# 9xVoice_MikeB_SMD_v1_0b.net
KiCad netlist of a schematic drawn in EAGLE
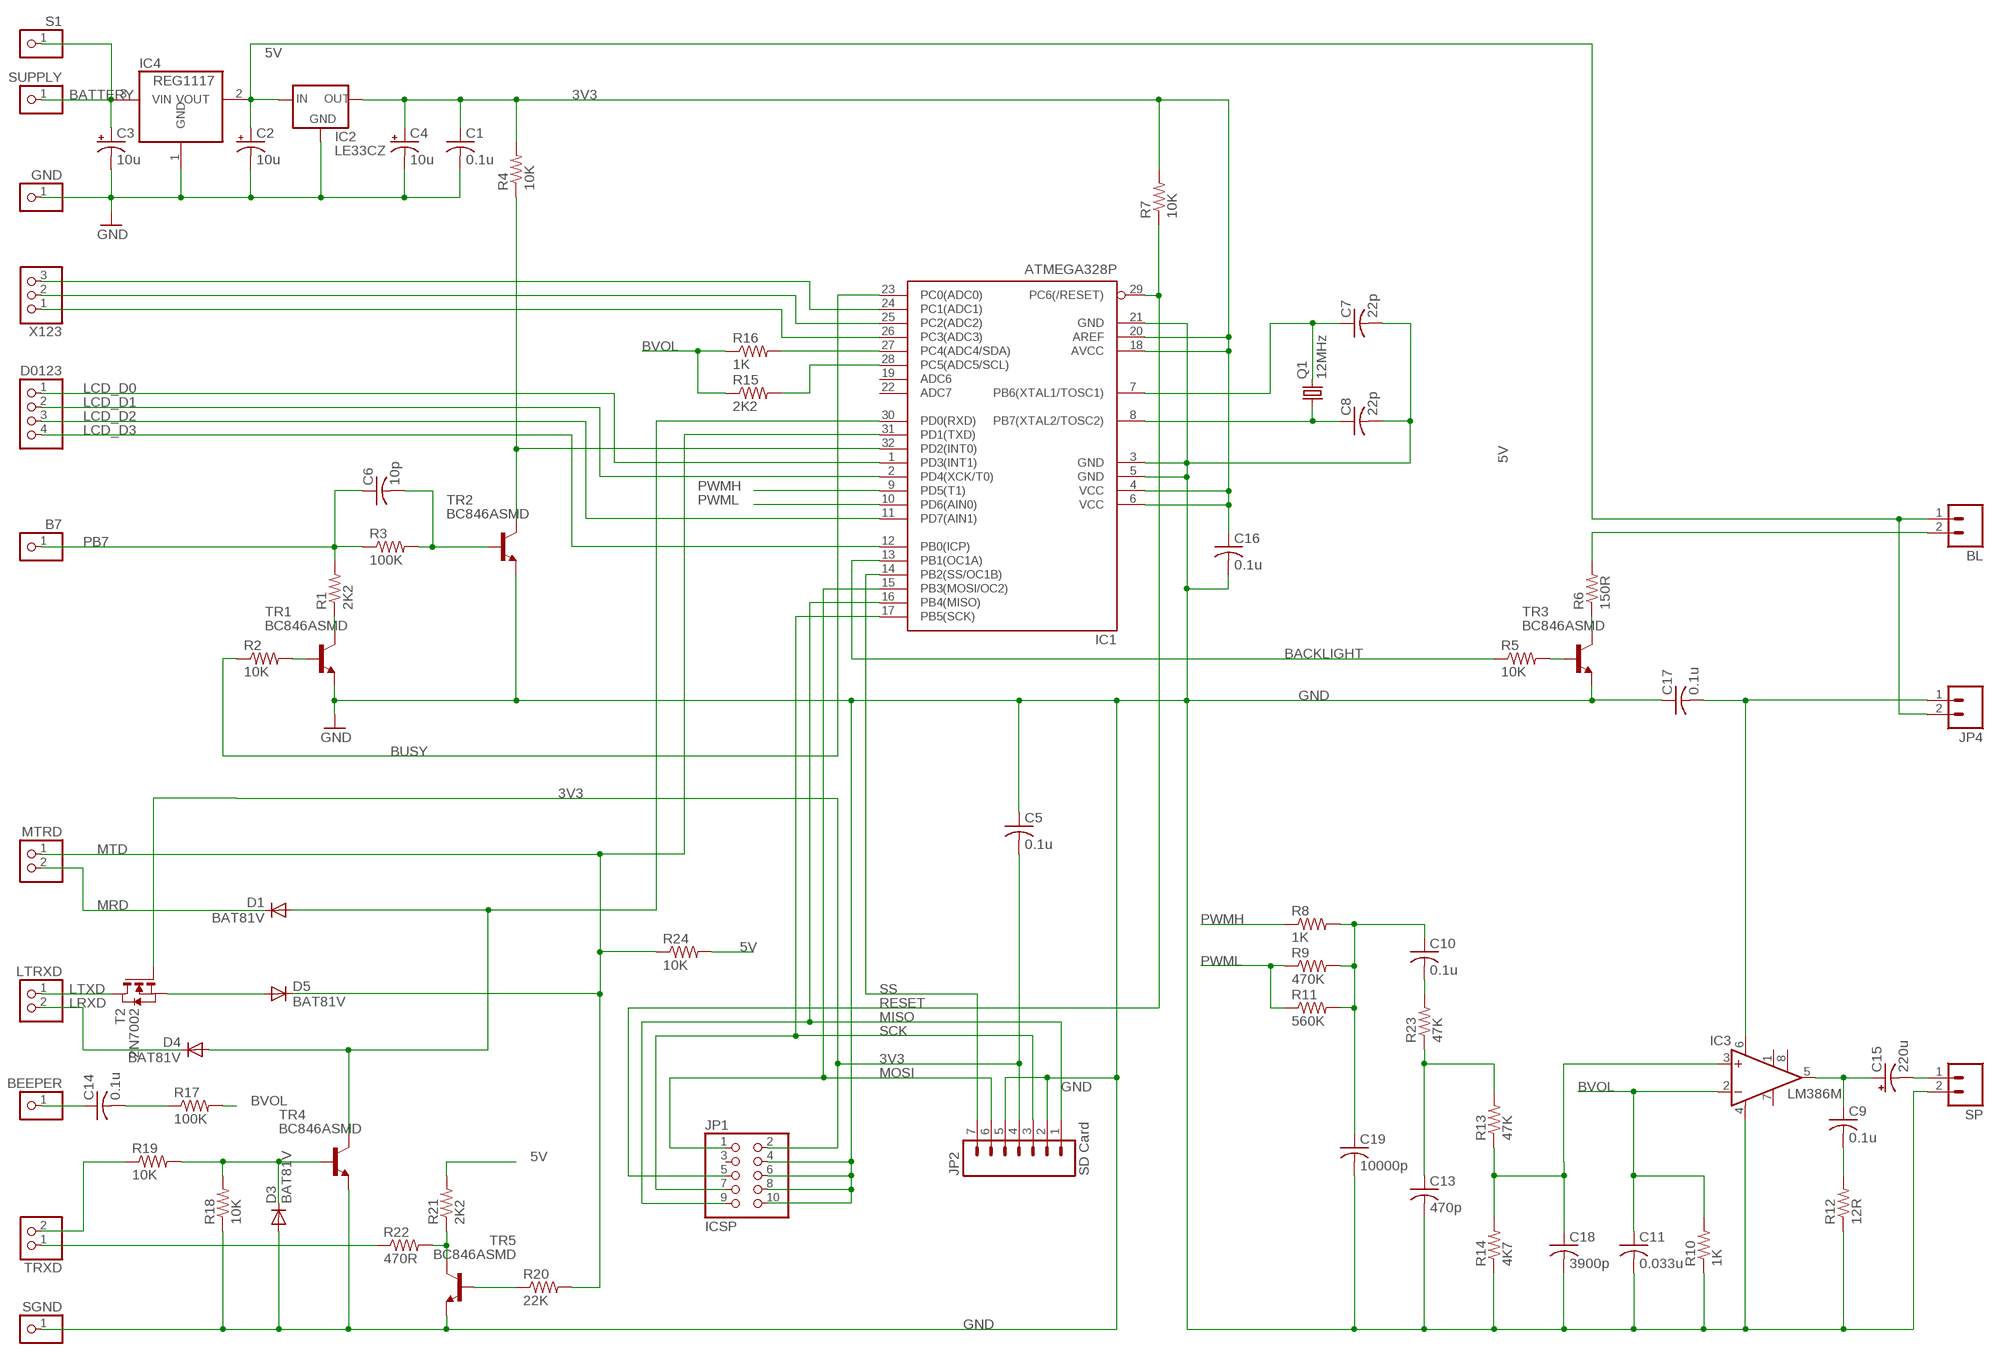
[diagram p0: schematic, sheet 1]

(export (version "E")
  (design (tool "Eeschema 10.0.6"))
  (components
    (comp (ref "B7")
      (value "PINHD-1X1")
      (footprint "eagle-import:1X01")
      (libsource (lib "eagle-import") (part "PINHD-1X1"))
    )
    (comp (ref "BEEPER")
      (value "PINHD-1X1")
      (footprint "eagle-import:1X01")
      (libsource (lib "eagle-import") (part "PINHD-1X1"))
    )
    (comp (ref "BL")
      (value "M02PTH")
      (footprint "eagle-import:1X02")
      (libsource (lib "eagle-import") (part "M02PTH"))
    )
    (comp (ref "C1")
      (value "0.1u")
      (footprint "eagle-import:C1206")
      (libsource (lib "eagle-import") (part "C-USC1206"))
    )
    (comp (ref "C2")
      (value "10u")
      (footprint "eagle-import:A_3216-18R")
      (libsource (lib "eagle-import") (part "CPOL-USA/3216-18R"))
    )
    (comp (ref "C3")
      (value "10u")
      (footprint "eagle-import:A_3216-18R")
      (libsource (lib "eagle-import") (part "CPOL-USA/3216-18R"))
    )
    (comp (ref "C4")
      (value "10u")
      (footprint "eagle-import:A_3216-18R")
      (libsource (lib "eagle-import") (part "CPOL-USA/3216-18R"))
    )
    (comp (ref "C5")
      (value "0.1u")
      (footprint "eagle-import:C1206")
      (libsource (lib "eagle-import") (part "C-USC1206"))
    )
    (comp (ref "C6")
      (value "10p")
      (footprint "eagle-import:C1206")
      (libsource (lib "eagle-import") (part "C-USC1206"))
    )
    (comp (ref "C7")
      (value "22p")
      (footprint "eagle-import:C1206")
      (libsource (lib "eagle-import") (part "C-USC1206"))
    )
    (comp (ref "C8")
      (value "22p")
      (footprint "eagle-import:C1206")
      (libsource (lib "eagle-import") (part "C-USC1206"))
    )
    (comp (ref "C9")
      (value "0.1u")
      (footprint "eagle-import:C1206")
      (libsource (lib "eagle-import") (part "C-USC1206"))
    )
    (comp (ref "C10")
      (value "0.1u")
      (footprint "eagle-import:C1206")
      (libsource (lib "eagle-import") (part "C-USC1206"))
    )
    (comp (ref "C11")
      (value "0.033u")
      (footprint "eagle-import:C1206")
      (libsource (lib "eagle-import") (part "C-USC1206"))
    )
    (comp (ref "C13")
      (value "470p")
      (footprint "eagle-import:C1206")
      (libsource (lib "eagle-import") (part "C-USC1206"))
    )
    (comp (ref "C14")
      (value "0.1u")
      (footprint "eagle-import:C1206")
      (libsource (lib "eagle-import") (part "C-USC1206"))
    )
    (comp (ref "C15")
      (value "220u")
      (footprint "eagle-import:CT7343")
      (libsource (lib "eagle-import") (part "CPOL-USCT7343"))
    )
    (comp (ref "C16")
      (value "0.1u")
      (footprint "eagle-import:C1206")
      (libsource (lib "eagle-import") (part "C-USC1206"))
    )
    (comp (ref "C17")
      (value "0.1u")
      (footprint "eagle-import:C1206")
      (libsource (lib "eagle-import") (part "C-USC1206"))
    )
    (comp (ref "C18")
      (value "3900p")
      (footprint "eagle-import:C1206")
      (libsource (lib "eagle-import") (part "C-USC1206"))
    )
    (comp (ref "C19")
      (value "10000p")
      (footprint "eagle-import:C1206")
      (libsource (lib "eagle-import") (part "C-USC1206"))
    )
    (comp (ref "D1")
      (value "BAT81V")
      (footprint "eagle-import:SOD123")
      (libsource (lib "eagle-import") (part "DIODE-SOD123"))
    )
    (comp (ref "D3")
      (value "BAT81V")
      (footprint "eagle-import:SOD123")
      (libsource (lib "eagle-import") (part "DIODE-SOD123"))
    )
    (comp (ref "D4")
      (value "BAT81V")
      (footprint "eagle-import:SOD123")
      (libsource (lib "eagle-import") (part "DIODE-SOD123"))
    )
    (comp (ref "D5")
      (value "BAT81V")
      (footprint "eagle-import:SOD123")
      (libsource (lib "eagle-import") (part "DIODE-SOD123"))
    )
    (comp (ref "D0123")
      (value "PINHD-1X4")
      (footprint "eagle-import:1X04")
      (libsource (lib "eagle-import") (part "PINHD-1X4"))
    )
    (comp (ref "GND")
      (value "PINHD-1X1")
      (footprint "eagle-import:1X01")
      (libsource (lib "eagle-import") (part "PINHD-1X1"))
    )
    (comp (ref "IC1")
      (value "ATMEGA328P")
      (footprint "eagle-import:TQFP32-08")
      (fields
        (field (name "MPN") "ATMEGA8-16AU")
        (field (name "MPN_1") "ATMEGA8-16AU")
        (field (name "OC_FARNELL") "9171371")
        (field (name "OC_NEWARK") "73M8863")
      )
      (libsource (lib "eagle-import") (part "MEGA8-AI"))
    )
    (comp (ref "IC2")
      (value "LE33CZ")
      (footprint "eagle-import:SOT23")
      (libsource (lib "eagle-import") (part "XC63FPM"))
    )
    (comp (ref "IC3")
      (value "LM386M")
      (footprint "eagle-import:SO08")
      (libsource (lib "eagle-import") (part "LM386?-M1"))
    )
    (comp (ref "IC4")
      (value "REG1117")
      (footprint "eagle-import:SOT223")
      (libsource (lib "eagle-import") (part "REG1117"))
    )
    (comp (ref "JP1")
      (value "ICSP")
      (footprint "eagle-import:2X05")
      (libsource (lib "eagle-import") (part "PINHD-2X5"))
    )
    (comp (ref "JP2")
      (value "SD Card")
      (footprint "eagle-import:1X07")
      (libsource (lib "eagle-import") (part "M07"))
    )
    (comp (ref "JP4")
      (value "M02PTH")
      (footprint "eagle-import:1X02")
      (libsource (lib "eagle-import") (part "M02PTH"))
    )
    (comp (ref "LTRXD")
      (value "PINHD-1X2")
      (footprint "eagle-import:1X02")
      (libsource (lib "eagle-import") (part "PINHD-1X2"))
    )
    (comp (ref "MTRD")
      (value "PINHD-1X2")
      (footprint "eagle-import:1X02")
      (libsource (lib "eagle-import") (part "PINHD-1X2"))
    )
    (comp (ref "Q1")
      (value "12MHz")
      (footprint "eagle-import:2-SMD")
      (libsource (lib "eagle-import") (part "7A"))
    )
    (comp (ref "R1")
      (value "2K2")
      (footprint "eagle-import:R1206")
      (libsource (lib "eagle-import") (part "R-US_R1206"))
    )
    (comp (ref "R2")
      (value "10K")
      (footprint "eagle-import:R1206")
      (libsource (lib "eagle-import") (part "R-US_R1206"))
    )
    (comp (ref "R3")
      (value "100K")
      (footprint "eagle-import:R1206")
      (libsource (lib "eagle-import") (part "R-US_R1206"))
    )
    (comp (ref "R4")
      (value "10K")
      (footprint "eagle-import:R1206")
      (libsource (lib "eagle-import") (part "R-US_R1206"))
    )
    (comp (ref "R5")
      (value "10K")
      (footprint "eagle-import:R1206")
      (libsource (lib "eagle-import") (part "R-US_R1206"))
    )
    (comp (ref "R6")
      (value "150R")
      (footprint "eagle-import:R1206")
      (libsource (lib "eagle-import") (part "R-US_R1206"))
    )
    (comp (ref "R7")
      (value "10K")
      (footprint "eagle-import:R1206")
      (libsource (lib "eagle-import") (part "R-US_R1206"))
    )
    (comp (ref "R8")
      (value "1K")
      (footprint "eagle-import:R1206")
      (libsource (lib "eagle-import") (part "R-US_R1206"))
    )
    (comp (ref "R9")
      (value "470K")
      (footprint "eagle-import:R1206")
      (libsource (lib "eagle-import") (part "R-US_R1206"))
    )
    (comp (ref "R10")
      (value "1K")
      (footprint "eagle-import:R1206")
      (libsource (lib "eagle-import") (part "R-US_R1206"))
    )
    (comp (ref "R11")
      (value "560K")
      (footprint "eagle-import:R1206")
      (libsource (lib "eagle-import") (part "R-US_R1206"))
    )
    (comp (ref "R12")
      (value "12R")
      (footprint "eagle-import:R1206")
      (libsource (lib "eagle-import") (part "R-US_R1206"))
    )
    (comp (ref "R13")
      (value "47K")
      (footprint "eagle-import:R1206")
      (libsource (lib "eagle-import") (part "R-US_R1206"))
    )
    (comp (ref "R14")
      (value "4K7")
      (footprint "eagle-import:R1206")
      (libsource (lib "eagle-import") (part "R-US_R1206"))
    )
    (comp (ref "R15")
      (value "2K2")
      (footprint "eagle-import:R1206")
      (libsource (lib "eagle-import") (part "R-US_R1206"))
    )
    (comp (ref "R16")
      (value "1K")
      (footprint "eagle-import:R1206")
      (libsource (lib "eagle-import") (part "R-US_R1206"))
    )
    (comp (ref "R17")
      (value "100K")
      (footprint "eagle-import:R1206")
      (libsource (lib "eagle-import") (part "R-US_R1206"))
    )
    (comp (ref "R18")
      (value "10K")
      (footprint "eagle-import:R1206")
      (libsource (lib "eagle-import") (part "R-US_R1206"))
    )
    (comp (ref "R19")
      (value "10K")
      (footprint "eagle-import:R1206")
      (libsource (lib "eagle-import") (part "R-US_R1206"))
    )
    (comp (ref "R20")
      (value "22K")
      (footprint "eagle-import:R1206")
      (libsource (lib "eagle-import") (part "R-US_R1206"))
    )
    (comp (ref "R21")
      (value "2K2")
      (footprint "eagle-import:R1206")
      (libsource (lib "eagle-import") (part "R-US_R1206"))
    )
    (comp (ref "R22")
      (value "470R")
      (footprint "eagle-import:R1206")
      (libsource (lib "eagle-import") (part "R-US_R1206"))
    )
    (comp (ref "R23")
      (value "47K")
      (footprint "eagle-import:R1206")
      (libsource (lib "eagle-import") (part "R-US_R1206"))
    )
    (comp (ref "R24")
      (value "10K")
      (footprint "eagle-import:R1206")
      (libsource (lib "eagle-import") (part "R-US_R1206"))
    )
    (comp (ref "S1")
      (value "PINHD-1X1")
      (footprint "eagle-import:1X01")
      (libsource (lib "eagle-import") (part "PINHD-1X1"))
    )
    (comp (ref "SGND")
      (value "PINHD-1X1")
      (footprint "eagle-import:1X01")
      (libsource (lib "eagle-import") (part "PINHD-1X1"))
    )
    (comp (ref "SP")
      (value "M02PTH")
      (footprint "eagle-import:1X02")
      (libsource (lib "eagle-import") (part "M02PTH"))
    )
    (comp (ref "SUPPLY")
      (value "PINHD-1X1")
      (footprint "eagle-import:1X01")
      (libsource (lib "eagle-import") (part "PINHD-1X1"))
    )
    (comp (ref "T2")
      (value "2N7002")
      (footprint "eagle-import:SOT-23")
      (libsource (lib "eagle-import") (part "NMOSSOT23"))
    )
    (comp (ref "TR1")
      (value "BC846ASMD")
      (footprint "eagle-import:SOT23")
      (libsource (lib "eagle-import") (part "BC846SMDA"))
    )
    (comp (ref "TR2")
      (value "BC846ASMD")
      (footprint "eagle-import:SOT23")
      (libsource (lib "eagle-import") (part "BC846SMDA"))
    )
    (comp (ref "TR3")
      (value "BC846ASMD")
      (footprint "eagle-import:SOT23")
      (libsource (lib "eagle-import") (part "BC846SMDA"))
    )
    (comp (ref "TR4")
      (value "BC846ASMD")
      (footprint "eagle-import:SOT23")
      (libsource (lib "eagle-import") (part "BC846SMDA"))
    )
    (comp (ref "TR5")
      (value "BC846ASMD")
      (footprint "eagle-import:SOT23")
      (libsource (lib "eagle-import") (part "BC846SMDA"))
    )
    (comp (ref "TRXD")
      (value "PINHD-1X2")
      (footprint "eagle-import:1X02")
      (libsource (lib "eagle-import") (part "PINHD-1X2"))
    )
    (comp (ref "X123")
      (value "PINHD-1X3")
      (footprint "eagle-import:1X03")
      (libsource (lib "eagle-import") (part "PINHD-1X3"))
    )
  )
  (nets
    (net (code "1") (name "/3V3") (class "Default")
      (node (ref "C1") (pin "1") (pinfunction "1_1") (pintype "passive"))
      (node (ref "C16") (pin "1") (pinfunction "1_1") (pintype "passive"))
      (node (ref "C4") (pin "+") (pinfunction "+_+") (pintype "passive"))
      (node (ref "C5") (pin "2") (pinfunction "2_2") (pintype "passive"))
      (node (ref "IC1") (pin "18") (pinfunction "AVCC_18") (pintype "power_in"))
      (node (ref "IC1") (pin "20") (pinfunction "AREF_20") (pintype "passive"))
      (node (ref "IC1") (pin "4") (pinfunction "VCC_4") (pintype "power_in"))
      (node (ref "IC1") (pin "6") (pinfunction "VCC_6") (pintype "power_in"))
      (node (ref "IC2") (pin "2") (pinfunction "OUT_2") (pintype "passive"))
      (node (ref "JP1") (pin "2") (pinfunction "2_2") (pintype "passive"))
      (node (ref "JP2") (pin "4") (pinfunction "4_4") (pintype "passive"))
      (node (ref "R4") (pin "2") (pinfunction "2_2") (pintype "passive"))
      (node (ref "R7") (pin "2") (pinfunction "2_2") (pintype "passive"))
      (node (ref "T2") (pin "3") (pinfunction "G_3") (pintype "passive"))
    )
    (net (code "2") (name "/5V") (class "Default")
      (node (ref "BL") (pin "1") (pinfunction "1_1") (pintype "passive"))
      (node (ref "C2") (pin "+") (pinfunction "+_+") (pintype "passive"))
      (node (ref "IC2") (pin "3") (pinfunction "IN_3") (pintype "input"))
      (node (ref "IC4") (pin "2") (pinfunction "VOUT_2") (pintype "output"))
      (node (ref "JP4") (pin "2") (pinfunction "2_2") (pintype "passive"))
      (node (ref "R21") (pin "2") (pinfunction "2_2") (pintype "passive"))
      (node (ref "R24") (pin "2") (pinfunction "2_2") (pintype "passive"))
    )
    (net (code "3") (name "/BACKLIGHT") (class "Default")
      (node (ref "IC1") (pin "13") (pinfunction "PB1(OC1A)_13") (pintype "bidirectional"))
      (node (ref "R5") (pin "1") (pinfunction "1_1") (pintype "passive"))
    )
    (net (code "4") (name "/BATTERY") (class "Default")
      (node (ref "C3") (pin "+") (pinfunction "+_+") (pintype "passive"))
      (node (ref "IC4") (pin "3") (pinfunction "VIN_3") (pintype "input"))
      (node (ref "S1") (pin "1") (pinfunction "1_1") (pintype "passive"))
      (node (ref "SUPPLY") (pin "1") (pinfunction "1_1") (pintype "passive"))
    )
    (net (code "5") (name "/BUSY") (class "Default")
      (node (ref "IC1") (pin "23") (pinfunction "PC0(ADC0)_23") (pintype "bidirectional"))
      (node (ref "R2") (pin "1") (pinfunction "1_1") (pintype "passive"))
    )
    (net (code "6") (name "/BVOL") (class "Default")
      (node (ref "C11") (pin "1") (pinfunction "1_1") (pintype "passive"))
      (node (ref "IC3") (pin "2") (pinfunction "-IN_2") (pintype "input"))
      (node (ref "R10") (pin "2") (pinfunction "2_2") (pintype "passive"))
      (node (ref "R15") (pin "1") (pinfunction "1_1") (pintype "passive"))
      (node (ref "R16") (pin "1") (pinfunction "1_1") (pintype "passive"))
      (node (ref "R17") (pin "2") (pinfunction "2_2") (pintype "passive"))
    )
    (net (code "7") (name "/LCD_D0") (class "Default")
      (node (ref "D0123") (pin "1") (pinfunction "1_1") (pintype "passive"))
      (node (ref "IC1") (pin "1") (pinfunction "PD3(INT1)_1") (pintype "bidirectional"))
    )
    (net (code "8") (name "/LCD_D1") (class "Default")
      (node (ref "D0123") (pin "2") (pinfunction "2_2") (pintype "passive"))
      (node (ref "IC1") (pin "2") (pinfunction "PD4(XCK/T0)_2") (pintype "bidirectional"))
    )
    (net (code "9") (name "/LCD_D2") (class "Default")
      (node (ref "D0123") (pin "3") (pinfunction "3_3") (pintype "passive"))
      (node (ref "IC1") (pin "11") (pinfunction "PD7(AIN1)_11") (pintype "bidirectional"))
    )
    (net (code "10") (name "/LCD_D3") (class "Default")
      (node (ref "D0123") (pin "4") (pinfunction "4_4") (pintype "passive"))
      (node (ref "IC1") (pin "12") (pinfunction "PB0(ICP)_12") (pintype "bidirectional"))
    )
    (net (code "11") (name "/LRXD") (class "Default")
      (node (ref "D4") (pin "C") (pinfunction "C_C") (pintype "passive"))
      (node (ref "LTRXD") (pin "2") (pinfunction "2_2") (pintype "passive"))
    )
    (net (code "12") (name "/LTXD") (class "Default")
      (node (ref "LTRXD") (pin "1") (pinfunction "1_1") (pintype "passive"))
      (node (ref "T2") (pin "1") (pinfunction "D_1") (pintype "passive"))
    )
    (net (code "13") (name "/MISO") (class "Default")
      (node (ref "IC1") (pin "16") (pinfunction "PB4(MISO)_16") (pintype "bidirectional"))
      (node (ref "JP1") (pin "9") (pinfunction "9_9") (pintype "passive"))
      (node (ref "JP2") (pin "1") (pinfunction "1_1") (pintype "passive"))
    )
    (net (code "14") (name "/MOSI") (class "Default")
      (node (ref "IC1") (pin "15") (pinfunction "PB3(MOSI/OC2)_15") (pintype "bidirectional"))
      (node (ref "JP1") (pin "1") (pinfunction "1_1") (pintype "passive"))
      (node (ref "JP2") (pin "6") (pinfunction "6_6") (pintype "passive"))
    )
    (net (code "15") (name "/MRD") (class "Default")
      (node (ref "D1") (pin "C") (pinfunction "C_C") (pintype "passive"))
      (node (ref "MTRD") (pin "2") (pinfunction "2_2") (pintype "passive"))
    )
    (net (code "16") (name "/MTD") (class "Default")
      (node (ref "D5") (pin "C") (pinfunction "C_C") (pintype "passive"))
      (node (ref "IC1") (pin "31") (pinfunction "PD1(TXD)_31") (pintype "bidirectional"))
      (node (ref "MTRD") (pin "1") (pinfunction "1_1") (pintype "passive"))
      (node (ref "R20") (pin "2") (pinfunction "2_2") (pintype "passive"))
      (node (ref "R24") (pin "1") (pinfunction "1_1") (pintype "passive"))
    )
    (net (code "17") (name "/PB7") (class "Default")
      (node (ref "B7") (pin "1") (pinfunction "1_1") (pintype "passive"))
      (node (ref "C6") (pin "1") (pinfunction "1_1") (pintype "passive"))
      (node (ref "R1") (pin "2") (pinfunction "2_2") (pintype "passive"))
      (node (ref "R3") (pin "1") (pinfunction "1_1") (pintype "passive"))
    )
    (net (code "18") (name "/PWMH") (class "Default")
      (node (ref "IC1") (pin "9") (pinfunction "PD5(T1)_9") (pintype "bidirectional"))
      (node (ref "R8") (pin "1") (pinfunction "1_1") (pintype "passive"))
    )
    (net (code "19") (name "/PWML") (class "Default")
      (node (ref "IC1") (pin "10") (pinfunction "PD6(AIN0)_10") (pintype "bidirectional"))
      (node (ref "R11") (pin "1") (pinfunction "1_1") (pintype "passive"))
      (node (ref "R9") (pin "1") (pinfunction "1_1") (pintype "passive"))
    )
    (net (code "20") (name "/RESET") (class "Default")
      (node (ref "IC1") (pin "29") (pinfunction "PC6(/RESET)_29") (pintype "bidirectional"))
      (node (ref "JP1") (pin "5") (pinfunction "5_5") (pintype "passive"))
      (node (ref "R7") (pin "1") (pinfunction "1_1") (pintype "passive"))
    )
    (net (code "21") (name "/SCK") (class "Default")
      (node (ref "IC1") (pin "17") (pinfunction "PB5(SCK)_17") (pintype "bidirectional"))
      (node (ref "JP1") (pin "7") (pinfunction "7_7") (pintype "passive"))
      (node (ref "JP2") (pin "3") (pinfunction "3_3") (pintype "passive"))
    )
    (net (code "22") (name "/SS") (class "Default")
      (node (ref "IC1") (pin "14") (pinfunction "PB2(SS/OC1B)_14") (pintype "bidirectional"))
      (node (ref "JP2") (pin "7") (pinfunction "7_7") (pintype "passive"))
    )
    (net (code "23") (name "GND") (class "Default")
      (node (ref "C1") (pin "2") (pinfunction "2_2") (pintype "passive"))
      (node (ref "C11") (pin "2") (pinfunction "2_2") (pintype "passive"))
      (node (ref "C13") (pin "2") (pinfunction "2_2") (pintype "passive"))
      (node (ref "C16") (pin "2") (pinfunction "2_2") (pintype "passive"))
      (node (ref "C17") (pin "1") (pinfunction "1_1") (pintype "passive"))
      (node (ref "C18") (pin "2") (pinfunction "2_2") (pintype "passive"))
      (node (ref "C19") (pin "2") (pinfunction "2_2") (pintype "passive"))
      (node (ref "C2") (pin "-") (pinfunction "-_-") (pintype "passive"))
      (node (ref "C3") (pin "-") (pinfunction "-_-") (pintype "passive"))
      (node (ref "C4") (pin "-") (pinfunction "-_-") (pintype "passive"))
      (node (ref "C5") (pin "1") (pinfunction "1_1") (pintype "passive"))
      (node (ref "C7") (pin "2") (pinfunction "2_2") (pintype "passive"))
      (node (ref "C8") (pin "2") (pinfunction "2_2") (pintype "passive"))
      (node (ref "D3") (pin "A") (pinfunction "A_A") (pintype "passive"))
      (node (ref "GND") (pin "1") (pinfunction "1_1") (pintype "passive"))
      (node (ref "IC1") (pin "21") (pinfunction "GND_21") (pintype "power_in"))
      (node (ref "IC1") (pin "3") (pinfunction "GND_3") (pintype "power_in"))
      (node (ref "IC1") (pin "5") (pinfunction "GND_5") (pintype "power_in"))
      (node (ref "IC2") (pin "1") (pinfunction "GND_1") (pintype "input"))
      (node (ref "IC3") (pin "4") (pinfunction "GND_4") (pintype "power_in"))
      (node (ref "IC4") (pin "1") (pinfunction "GND_1") (pintype "power_in"))
      (node (ref "JP1") (pin "10") (pinfunction "10_10") (pintype "passive"))
      (node (ref "JP1") (pin "4") (pinfunction "4_4") (pintype "passive"))
      (node (ref "JP1") (pin "6") (pinfunction "6_6") (pintype "passive"))
      (node (ref "JP1") (pin "8") (pinfunction "8_8") (pintype "passive"))
      (node (ref "JP2") (pin "2") (pinfunction "2_2") (pintype "passive"))
      (node (ref "JP2") (pin "5") (pinfunction "5_5") (pintype "passive"))
      (node (ref "R10") (pin "1") (pinfunction "1_1") (pintype "passive"))
      (node (ref "R12") (pin "1") (pinfunction "1_1") (pintype "passive"))
      (node (ref "R14") (pin "1") (pinfunction "1_1") (pintype "passive"))
      (node (ref "R18") (pin "1") (pinfunction "1_1") (pintype "passive"))
      (node (ref "SGND") (pin "1") (pinfunction "1_1") (pintype "passive"))
      (node (ref "SP") (pin "2") (pinfunction "2_2") (pintype "passive"))
      (node (ref "TR1") (pin "2") (pinfunction "E_2") (pintype "passive"))
      (node (ref "TR2") (pin "2") (pinfunction "E_2") (pintype "passive"))
      (node (ref "TR3") (pin "2") (pinfunction "E_2") (pintype "passive"))
      (node (ref "TR4") (pin "2") (pinfunction "E_2") (pintype "passive"))
      (node (ref "TR5") (pin "2") (pinfunction "E_2") (pintype "passive"))
    )
    (net (code "24") (name "Net-(BEEPER-Pad1)") (class "Default")
      (node (ref "BEEPER") (pin "1") (pinfunction "1_1") (pintype "passive"))
      (node (ref "C14") (pin "1") (pinfunction "1_1") (pintype "passive"))
    )
    (net (code "25") (name "Net-(BL-Pad2)") (class "Default")
      (node (ref "BL") (pin "2") (pinfunction "2_2") (pintype "passive"))
      (node (ref "R6") (pin "2") (pinfunction "2_2") (pintype "passive"))
    )
    (net (code "26") (name "Net-(C9-Pad2)") (class "Default")
      (node (ref "C9") (pin "2") (pinfunction "2_2") (pintype "passive"))
      (node (ref "R12") (pin "2") (pinfunction "2_2") (pintype "passive"))
    )
    (net (code "27") (name "Net-(C10-Pad1)") (class "Default")
      (node (ref "C10") (pin "1") (pinfunction "1_1") (pintype "passive"))
      (node (ref "C19") (pin "1") (pinfunction "1_1") (pintype "passive"))
      (node (ref "R11") (pin "2") (pinfunction "2_2") (pintype "passive"))
      (node (ref "R8") (pin "2") (pinfunction "2_2") (pintype "passive"))
      (node (ref "R9") (pin "2") (pinfunction "2_2") (pintype "passive"))
    )
    (net (code "28") (name "Net-(C10-Pad2)") (class "Default")
      (node (ref "C10") (pin "2") (pinfunction "2_2") (pintype "passive"))
      (node (ref "R23") (pin "2") (pinfunction "2_2") (pintype "passive"))
    )
    (net (code "29") (name "Net-(C13-Pad1)") (class "Default")
      (node (ref "C13") (pin "1") (pinfunction "1_1") (pintype "passive"))
      (node (ref "R13") (pin "2") (pinfunction "2_2") (pintype "passive"))
      (node (ref "R23") (pin "1") (pinfunction "1_1") (pintype "passive"))
    )
    (net (code "30") (name "Net-(C14-Pad2)") (class "Default")
      (node (ref "C14") (pin "2") (pinfunction "2_2") (pintype "passive"))
      (node (ref "R17") (pin "1") (pinfunction "1_1") (pintype "passive"))
    )
    (net (code "31") (name "Net-(C15-Pad-)") (class "Default")
      (node (ref "C15") (pin "-") (pinfunction "-_-") (pintype "passive"))
      (node (ref "SP") (pin "1") (pinfunction "1_1") (pintype "passive"))
    )
    (net (code "32") (name "Net-(IC1-PB6(XTAL1{slash}TOSC1))") (class "Default")
      (node (ref "C7") (pin "1") (pinfunction "1_1") (pintype "passive"))
      (node (ref "IC1") (pin "7") (pinfunction "PB6(XTAL1/TOSC1)_7") (pintype "bidirectional"))
      (node (ref "Q1") (pin "P$2") (pinfunction "2_P$2") (pintype "passive"))
    )
    (net (code "33") (name "Net-(IC1-PB7(XTAL2{slash}TOSC2))") (class "Default")
      (node (ref "C8") (pin "1") (pinfunction "1_1") (pintype "passive"))
      (node (ref "IC1") (pin "8") (pinfunction "PB7(XTAL2/TOSC2)_8") (pintype "bidirectional"))
      (node (ref "Q1") (pin "P$1") (pinfunction "1_P$1") (pintype "passive"))
    )
    (net (code "34") (name "Net-(IC1-PC1(ADC1))") (class "Default")
      (node (ref "IC1") (pin "24") (pinfunction "PC1(ADC1)_24") (pintype "bidirectional"))
      (node (ref "X123") (pin "3") (pinfunction "3_3") (pintype "passive"))
    )
    (net (code "35") (name "Net-(IC1-PC2(ADC2))") (class "Default")
      (node (ref "IC1") (pin "25") (pinfunction "PC2(ADC2)_25") (pintype "bidirectional"))
      (node (ref "X123") (pin "2") (pinfunction "2_2") (pintype "passive"))
    )
    (net (code "36") (name "Net-(IC1-PC3(ADC3))") (class "Default")
      (node (ref "IC1") (pin "26") (pinfunction "PC3(ADC3)_26") (pintype "bidirectional"))
      (node (ref "X123") (pin "1") (pinfunction "1_1") (pintype "passive"))
    )
    (net (code "37") (name "Net-(IC1-PC4(ADC4{slash}SDA))") (class "Default")
      (node (ref "IC1") (pin "27") (pinfunction "PC4(ADC4/SDA)_27") (pintype "bidirectional"))
      (node (ref "R16") (pin "2") (pinfunction "2_2") (pintype "passive"))
    )
    (net (code "38") (name "Net-(IC1-PC5(ADC5{slash}SCL))") (class "Default")
      (node (ref "IC1") (pin "28") (pinfunction "PC5(ADC5/SCL)_28") (pintype "bidirectional"))
      (node (ref "R15") (pin "2") (pinfunction "2_2") (pintype "passive"))
    )
    (net (code "39") (name "Net-(IC1-PD0(RXD))") (class "Default")
      (node (ref "D1") (pin "A") (pinfunction "A_A") (pintype "passive"))
      (node (ref "D4") (pin "A") (pinfunction "A_A") (pintype "passive"))
      (node (ref "IC1") (pin "30") (pinfunction "PD0(RXD)_30") (pintype "bidirectional"))
      (node (ref "TR4") (pin "3") (pinfunction "C_3") (pintype "passive"))
    )
    (net (code "40") (name "Net-(IC1-PD2(INT0))") (class "Default")
      (node (ref "IC1") (pin "32") (pinfunction "PD2(INT0)_32") (pintype "bidirectional"))
      (node (ref "R4") (pin "1") (pinfunction "1_1") (pintype "passive"))
      (node (ref "TR2") (pin "3") (pinfunction "C_3") (pintype "passive"))
    )
    (net (code "41") (name "Net-(IC3-+IN)") (class "Default")
      (node (ref "C18") (pin "1") (pinfunction "1_1") (pintype "passive"))
      (node (ref "IC3") (pin "3") (pinfunction "+IN_3") (pintype "input"))
      (node (ref "R13") (pin "1") (pinfunction "1_1") (pintype "passive"))
      (node (ref "R14") (pin "2") (pinfunction "2_2") (pintype "passive"))
    )
    (net (code "42") (name "Net-(IC3-OUT)") (class "Default")
      (node (ref "C15") (pin "+") (pinfunction "+_+") (pintype "passive"))
      (node (ref "C9") (pin "1") (pinfunction "1_1") (pintype "passive"))
      (node (ref "IC3") (pin "5") (pinfunction "OUT_5") (pintype "output"))
    )
    (net (code "43") (name "Net-(IC3-VS)") (class "Default")
      (node (ref "C17") (pin "2") (pinfunction "2_2") (pintype "passive"))
      (node (ref "IC3") (pin "6") (pinfunction "VS_6") (pintype "power_in"))
      (node (ref "JP4") (pin "1") (pinfunction "1_1") (pintype "passive"))
    )
    (net (code "44") (name "Net-(R19-Pad1)") (class "Default")
      (node (ref "R19") (pin "1") (pinfunction "1_1") (pintype "passive"))
      (node (ref "TRXD") (pin "2") (pinfunction "2_2") (pintype "passive"))
    )
    (net (code "45") (name "Net-(R22-Pad1)") (class "Default")
      (node (ref "R22") (pin "1") (pinfunction "1_1") (pintype "passive"))
      (node (ref "TRXD") (pin "1") (pinfunction "1_1") (pintype "passive"))
    )
    (net (code "46") (name "Net-(T2-S)") (class "Default")
      (node (ref "D5") (pin "A") (pinfunction "A_A") (pintype "passive"))
      (node (ref "T2") (pin "2") (pinfunction "S_2") (pintype "passive"))
    )
    (net (code "47") (name "Net-(TR1-B)") (class "Default")
      (node (ref "R2") (pin "2") (pinfunction "2_2") (pintype "passive"))
      (node (ref "TR1") (pin "1") (pinfunction "B_1") (pintype "passive"))
    )
    (net (code "48") (name "Net-(TR1-C)") (class "Default")
      (node (ref "R1") (pin "1") (pinfunction "1_1") (pintype "passive"))
      (node (ref "TR1") (pin "3") (pinfunction "C_3") (pintype "passive"))
    )
    (net (code "49") (name "Net-(TR2-B)") (class "Default")
      (node (ref "C6") (pin "2") (pinfunction "2_2") (pintype "passive"))
      (node (ref "R3") (pin "2") (pinfunction "2_2") (pintype "passive"))
      (node (ref "TR2") (pin "1") (pinfunction "B_1") (pintype "passive"))
    )
    (net (code "50") (name "Net-(TR3-B)") (class "Default")
      (node (ref "R5") (pin "2") (pinfunction "2_2") (pintype "passive"))
      (node (ref "TR3") (pin "1") (pinfunction "B_1") (pintype "passive"))
    )
    (net (code "51") (name "Net-(TR3-C)") (class "Default")
      (node (ref "R6") (pin "1") (pinfunction "1_1") (pintype "passive"))
      (node (ref "TR3") (pin "3") (pinfunction "C_3") (pintype "passive"))
    )
    (net (code "52") (name "Net-(TR4-B)") (class "Default")
      (node (ref "D3") (pin "C") (pinfunction "C_C") (pintype "passive"))
      (node (ref "R18") (pin "2") (pinfunction "2_2") (pintype "passive"))
      (node (ref "R19") (pin "2") (pinfunction "2_2") (pintype "passive"))
      (node (ref "TR4") (pin "1") (pinfunction "B_1") (pintype "passive"))
    )
    (net (code "53") (name "Net-(TR5-B)") (class "Default")
      (node (ref "R20") (pin "1") (pinfunction "1_1") (pintype "passive"))
      (node (ref "TR5") (pin "1") (pinfunction "B_1") (pintype "passive"))
    )
    (net (code "54") (name "Net-(TR5-C)") (class "Default")
      (node (ref "R21") (pin "1") (pinfunction "1_1") (pintype "passive"))
      (node (ref "R22") (pin "2") (pinfunction "2_2") (pintype "passive"))
      (node (ref "TR5") (pin "3") (pinfunction "C_3") (pintype "passive"))
    )
    (net (code "55") (name "unconnected-(IC1-ADC6-Pad19)") (class "Default")
      (node (ref "IC1") (pin "19") (pinfunction "ADC6_19") (pintype "bidirectional"))
    )
    (net (code "56") (name "unconnected-(IC1-ADC7-Pad22)") (class "Default")
      (node (ref "IC1") (pin "22") (pinfunction "ADC7_22") (pintype "bidirectional"))
    )
    (net (code "57") (name "unconnected-(IC3-BYPASS-Pad7)") (class "Default")
      (node (ref "IC3") (pin "7") (pinfunction "BYPASS_7") (pintype "passive"))
    )
    (net (code "58") (name "unconnected-(IC3-GAIN-Pad1)") (class "Default")
      (node (ref "IC3") (pin "1") (pinfunction "GAIN_1") (pintype "passive"))
    )
    (net (code "59") (name "unconnected-(IC3-GAIN-Pad8)") (class "Default")
      (node (ref "IC3") (pin "8") (pinfunction "GAIN_8") (pintype "passive"))
    )
    (net (code "60") (name "unconnected-(JP1-Pad3)") (class "Default")
      (node (ref "JP1") (pin "3") (pinfunction "3_3") (pintype "passive"))
    )
  )
)
